# Receiver.net
KiCad netlist of a schematic drawn in Altium Designer
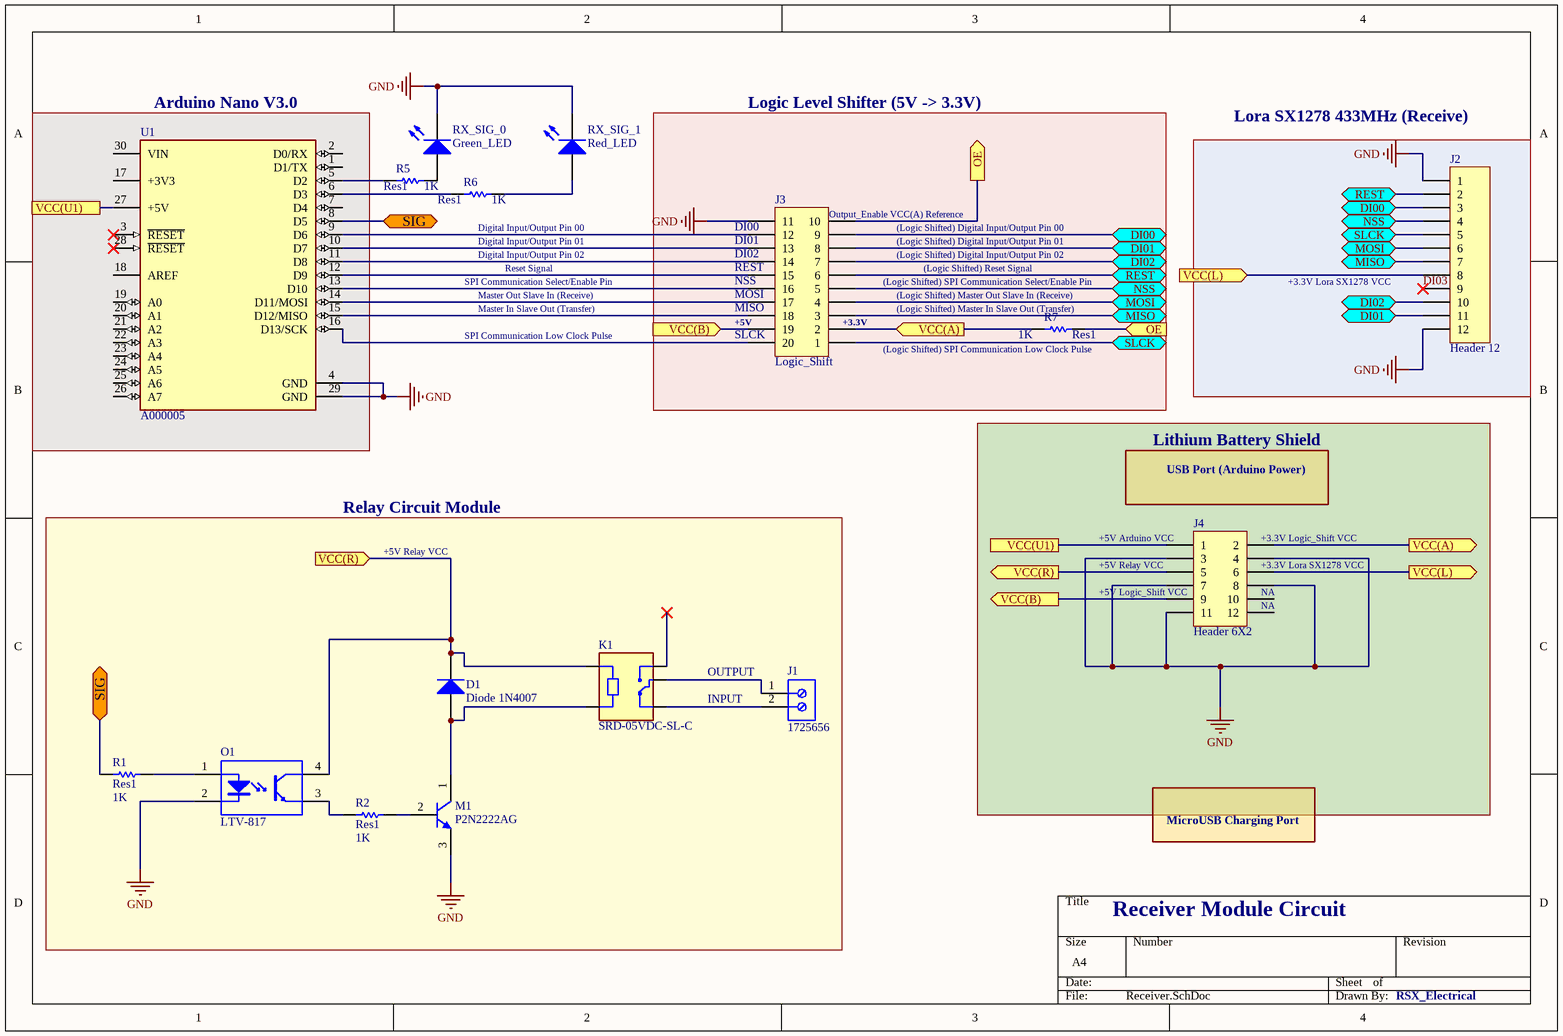
[diagram p0: Receiver.SchDoc]

(export (version "E")
  (design (tool "Eeschema 10.0.6"))
  (components
    (comp (ref "D1")
      (value "Diode 1N4007")
      (footprint "DO-41")
      (description "1 Amp General Purpose Rectifier")
      (fields (field (name "PUBLISHER") "Altium Limited"))
      (libsource (lib "Miscellaneous Devices") (part "Diode 1N4007"))
    )
    (comp (ref "J1")
      (value "1725656")
      (footprint "PHOE-1725656-2")
      (description "Male Header, Pitch 2.54 mm, 1 x 2 Position, Height 9 mm, Tail Length 3.5 mm")
      (fields (field (name "MANUFACTURER") "Phoenix Contact"))
      (libsource (lib "Altium Content Vault") (part "CN-1P-F-TB2"))
    )
    (comp (ref "J2")
      (value "Header 12")
      (footprint "LORA Sx1278")
      (description "Header, 12-Pin")
      (fields (field (name "PUBLISHER") "Altium Limited"))
      (libsource (lib "Miscellaneous Connectors") (part "Header 12"))
    )
    (comp (ref "J3")
      (value "Logic_Shift")
      (footprint "DIP2SSOP20")
      (description "Header, 10-Pin, Dual row")
      (fields (field (name "PUBLISHER") "Altium Limited"))
      (libsource (lib "Miscellaneous Connectors") (part "Header 10X2"))
    )
    (comp (ref "J4")
      (value "Header 6X2")
      (footprint "3.3V/5V Battery Shield")
      (description "Header, 6-Pin, Dual row")
      (fields (field (name "PUBLISHER") "Altium Limited"))
      (libsource (lib "Miscellaneous Connectors") (part "Header 6X2"))
    )
    (comp (ref "K1")
      (value "SRD-05VDC-SL-C")
      (footprint "RELAY_SRD-05VDC-SL-C")
      (fields (field (name "MF") "Songle Relay"))
      (libsource (lib "SRD-05VDC-SL-C") (part "SRD-05VDC-SL-C"))
    )
    (comp (ref "M1")
      (value "P2N2222AG")
      (footprint "ONSC-TO-92-3-29-11")
      (description "Amplifier Transistor, NPN Silicon, 3-Pin TO-92, Pb-Free, Bulk Box")
      (fields (field (name "MANUFACTURER") "On Semiconductor"))
      (libsource (lib "Altium Content Vault") (part "ONSC-NPN-C1B2E3-3"))
    )
    (comp (ref "O1")
      (value "LTV-817")
      (footprint "LTST-LTV-817-4")
      (fields (field (name "MANUFACTURER") "Lite-On"))
      (libsource (lib "Altium Content Vault") (part "OPTO-AKEC-4"))
    )
    (comp (ref "R1")
      (value "Res1")
      (footprint "AXIAL-0.3")
      (description "Resistor")
      (fields (field (name "ALTIUM_VALUE") "1K") (field (name "PUBLISHER") "Altium Limited"))
      (libsource (lib "Miscellaneous Devices") (part "Res1"))
    )
    (comp (ref "R2")
      (value "Res1")
      (footprint "AXIAL-0.3")
      (description "Resistor")
      (fields (field (name "ALTIUM_VALUE") "1K") (field (name "PUBLISHER") "Altium Limited"))
      (libsource (lib "Miscellaneous Devices") (part "Res1"))
    )
    (comp (ref "R5")
      (value "Res1")
      (footprint "AXIAL-0.3")
      (description "Resistor")
      (fields (field (name "ALTIUM_VALUE") "1K") (field (name "PUBLISHER") "Altium Limited"))
      (libsource (lib "Miscellaneous Devices") (part "Res1"))
    )
    (comp (ref "R6")
      (value "Res1")
      (footprint "AXIAL-0.3")
      (description "Resistor")
      (fields (field (name "ALTIUM_VALUE") "1K") (field (name "PUBLISHER") "Altium Limited"))
      (libsource (lib "Miscellaneous Devices") (part "Res1"))
    )
    (comp (ref "R7")
      (value "Res1")
      (footprint "AXIAL-0.3")
      (description "Resistor")
      (fields (field (name "ALTIUM_VALUE") "1K") (field (name "PUBLISHER") "Altium Limited"))
      (libsource (lib "Miscellaneous Devices") (part "Res1"))
    )
    (comp (ref "RX_SIG_0")
      (value "Green_LED")
      (footprint "LED-0")
      (description "Typical INFRARED GaAs LED")
      (fields (field (name "PUBLISHER") "Altium Limited"))
      (libsource (lib "Miscellaneous Devices") (part "LED0"))
    )
    (comp (ref "RX_SIG_1")
      (value "Red_LED")
      (footprint "LED-0")
      (description "Typical INFRARED GaAs LED")
      (fields (field (name "PUBLISHER") "Altium Limited"))
      (libsource (lib "Miscellaneous Devices") (part "LED0"))
    )
    (comp (ref "U1")
      (value "A000005")
      (footprint "FP-A000005-MFG")
      (description "ARDUINO NANO ATMEGA328 EVAL BRD")
      (libsource (lib "Altium Content Vault") (part "d190c066e99afd1c6882cf92e11b2cc"))
    )
  )
  (nets
    (net (code "1") (name "/DI00") (class "Default")
      (node (ref "J2") (pin "3") (pinfunction "3_3") (pintype "passive"))
      (node (ref "J3") (pin "9") (pinfunction "9_9") (pintype "passive"))
    )
    (net (code "2") (name "/DI01") (class "Default")
      (node (ref "J2") (pin "11") (pinfunction "11_11") (pintype "passive"))
      (node (ref "J3") (pin "8") (pinfunction "8_8") (pintype "passive"))
    )
    (net (code "3") (name "/DI02") (class "Default")
      (node (ref "J2") (pin "10") (pinfunction "10_10") (pintype "passive"))
      (node (ref "J3") (pin "7") (pinfunction "7_7") (pintype "passive"))
    )
    (net (code "4") (name "/DI03") (class "Default")
      (node (ref "J2") (pin "9") (pinfunction "9_9") (pintype "passive+no_connect"))
    )
    (net (code "5") (name "/MISO") (class "Default")
      (node (ref "J2") (pin "7") (pinfunction "7_7") (pintype "passive"))
      (node (ref "J3") (pin "3") (pinfunction "3_3") (pintype "passive"))
    )
    (net (code "6") (name "/MOSI") (class "Default")
      (node (ref "J2") (pin "6") (pinfunction "6_6") (pintype "passive"))
      (node (ref "J3") (pin "4") (pinfunction "4_4") (pintype "passive"))
    )
    (net (code "7") (name "/NSS") (class "Default")
      (node (ref "J2") (pin "4") (pinfunction "4_4") (pintype "passive"))
      (node (ref "J3") (pin "5") (pinfunction "5_5") (pintype "passive"))
    )
    (net (code "8") (name "/OE") (class "Default")
      (node (ref "J3") (pin "10") (pinfunction "10_10") (pintype "passive"))
      (node (ref "R7") (pin "1") (pinfunction "1_1") (pintype "passive"))
    )
    (net (code "9") (name "/REST") (class "Default")
      (node (ref "J2") (pin "2") (pinfunction "2_2") (pintype "passive"))
      (node (ref "J3") (pin "6") (pinfunction "6_6") (pintype "passive"))
    )
    (net (code "10") (name "/SIG") (class "Default")
      (node (ref "R1") (pin "2") (pinfunction "2_2") (pintype "passive"))
      (node (ref "U1") (pin "8") (pinfunction "D5_8") (pintype "bidirectional"))
    )
    (net (code "11") (name "/SLCK") (class "Default")
      (node (ref "J2") (pin "5") (pinfunction "5_5") (pintype "passive"))
      (node (ref "J3") (pin "1") (pinfunction "1_1") (pintype "passive"))
    )
    (net (code "12") (name "/VCC(A)") (class "Default")
      (node (ref "J3") (pin "2") (pinfunction "2_2") (pintype "passive"))
      (node (ref "J4") (pin "2") (pinfunction "2_2") (pintype "passive"))
      (node (ref "R7") (pin "2") (pinfunction "2_2") (pintype "passive"))
    )
    (net (code "13") (name "/VCC(B)") (class "Default")
      (node (ref "J3") (pin "19") (pinfunction "19_19") (pintype "passive"))
      (node (ref "J4") (pin "9") (pinfunction "9_9") (pintype "passive"))
    )
    (net (code "14") (name "/VCC(L)") (class "Default")
      (node (ref "J2") (pin "8") (pinfunction "8_8") (pintype "passive"))
      (node (ref "J4") (pin "6") (pinfunction "6_6") (pintype "passive"))
    )
    (net (code "15") (name "/VCC(R)") (class "Default")
      (node (ref "D1") (pin "2") (pinfunction "K_2") (pintype "passive"))
      (node (ref "J4") (pin "5") (pinfunction "5_5") (pintype "passive"))
      (node (ref "K1") (pin "A1") (pinfunction "A1_A1") (pintype "passive"))
      (node (ref "O1") (pin "4") (pinfunction "COLLECTOR_4") (pintype "passive"))
    )
    (net (code "16") (name "/VCC(U1)") (class "Default")
      (node (ref "J4") (pin "1") (pinfunction "1_1") (pintype "passive"))
      (node (ref "U1") (pin "27") (pinfunction "+5V_27") (pintype "power_in"))
    )
    (net (code "17") (name "GND") (class "Default")
      (node (ref "J2") (pin "1") (pinfunction "1_1") (pintype "passive"))
      (node (ref "J2") (pin "12") (pinfunction "12_12") (pintype "passive"))
      (node (ref "J3") (pin "11") (pinfunction "11_11") (pintype "passive"))
      (node (ref "J4") (pin "11") (pinfunction "11_11") (pintype "passive"))
      (node (ref "J4") (pin "3") (pinfunction "3_3") (pintype "passive"))
      (node (ref "J4") (pin "4") (pinfunction "4_4") (pintype "passive"))
      (node (ref "J4") (pin "7") (pinfunction "7_7") (pintype "passive"))
      (node (ref "J4") (pin "8") (pinfunction "8_8") (pintype "passive"))
      (node (ref "M1") (pin "3") (pinfunction "E_3") (pintype "passive"))
      (node (ref "O1") (pin "2") (pinfunction "CATHODE_2") (pintype "passive"))
      (node (ref "RX_SIG_0") (pin "2") (pinfunction "K_2") (pintype "passive"))
      (node (ref "RX_SIG_1") (pin "2") (pinfunction "K_2") (pintype "passive"))
      (node (ref "U1") (pin "29") (pinfunction "GND_29") (pintype "power_in"))
      (node (ref "U1") (pin "4") (pinfunction "GND_4") (pintype "power_in"))
    )
    (net (code "18") (name "Net-(D1-A)") (class "Default")
      (node (ref "D1") (pin "1") (pinfunction "A_1") (pintype "passive"))
      (node (ref "K1") (pin "A2") (pinfunction "A2_A2") (pintype "passive"))
      (node (ref "M1") (pin "1") (pinfunction "C_1") (pintype "passive"))
    )
    (net (code "19") (name "Net-(J1-Pad1)") (class "Default")
      (node (ref "J1") (pin "1") (pinfunction "1_1") (pintype "passive"))
      (node (ref "K1") (pin "COM") (pinfunction "COM_COM") (pintype "passive"))
    )
    (net (code "20") (name "Net-(J1-Pad2)") (class "Default")
      (node (ref "J1") (pin "2") (pinfunction "2_2") (pintype "passive"))
      (node (ref "K1") (pin "NC") (pinfunction "NC_NC") (pintype "passive"))
    )
    (net (code "21") (name "Net-(M1-B)") (class "Default")
      (node (ref "M1") (pin "2") (pinfunction "B_2") (pintype "passive"))
      (node (ref "R2") (pin "2") (pinfunction "2_2") (pintype "passive"))
    )
    (net (code "22") (name "Net-(O1-ANODE)") (class "Default")
      (node (ref "O1") (pin "1") (pinfunction "ANODE_1") (pintype "passive"))
      (node (ref "R1") (pin "1") (pinfunction "1_1") (pintype "passive"))
    )
    (net (code "23") (name "Net-(O1-EMITTER)") (class "Default")
      (node (ref "O1") (pin "3") (pinfunction "EMITTER_3") (pintype "passive"))
      (node (ref "R2") (pin "1") (pinfunction "1_1") (pintype "passive"))
    )
    (net (code "24") (name "Net-(RX_SIG_0-A)") (class "Default")
      (node (ref "R5") (pin "1") (pinfunction "1_1") (pintype "passive"))
      (node (ref "RX_SIG_0") (pin "1") (pinfunction "A_1") (pintype "passive"))
    )
    (net (code "25") (name "Net-(RX_SIG_1-A)") (class "Default")
      (node (ref "R6") (pin "1") (pinfunction "1_1") (pintype "passive"))
      (node (ref "RX_SIG_1") (pin "1") (pinfunction "A_1") (pintype "passive"))
    )
    (net (code "26") (name "Net-(U1-D2)") (class "Default")
      (node (ref "R5") (pin "2") (pinfunction "2_2") (pintype "passive"))
      (node (ref "U1") (pin "5") (pinfunction "D2_5") (pintype "bidirectional"))
    )
    (net (code "27") (name "Net-(U1-D3)") (class "Default")
      (node (ref "R6") (pin "2") (pinfunction "2_2") (pintype "passive"))
      (node (ref "U1") (pin "6") (pinfunction "D3_6") (pintype "bidirectional"))
    )
    (net (code "28") (name "Net-(U1-D6)") (class "Default")
      (node (ref "J3") (pin "12") (pinfunction "12_12") (pintype "passive"))
      (node (ref "U1") (pin "9") (pinfunction "D6_9") (pintype "bidirectional"))
    )
    (net (code "29") (name "Net-(U1-D7)") (class "Default")
      (node (ref "J3") (pin "13") (pinfunction "13_13") (pintype "passive"))
      (node (ref "U1") (pin "10") (pinfunction "D7_10") (pintype "bidirectional"))
    )
    (net (code "30") (name "Net-(U1-D8)") (class "Default")
      (node (ref "J3") (pin "14") (pinfunction "14_14") (pintype "passive"))
      (node (ref "U1") (pin "11") (pinfunction "D8_11") (pintype "bidirectional"))
    )
    (net (code "31") (name "Net-(U1-D9)") (class "Default")
      (node (ref "J3") (pin "15") (pinfunction "15_15") (pintype "passive"))
      (node (ref "U1") (pin "12") (pinfunction "D9_12") (pintype "bidirectional"))
    )
    (net (code "32") (name "Net-(U1-D10)") (class "Default")
      (node (ref "J3") (pin "16") (pinfunction "16_16") (pintype "passive"))
      (node (ref "U1") (pin "13") (pinfunction "D10_13") (pintype "bidirectional"))
    )
    (net (code "33") (name "Net-(U1-D11{slash}MOSI)") (class "Default")
      (node (ref "J3") (pin "17") (pinfunction "17_17") (pintype "passive"))
      (node (ref "U1") (pin "14") (pinfunction "D11/MOSI_14") (pintype "bidirectional"))
    )
    (net (code "34") (name "Net-(U1-D12{slash}MISO)") (class "Default")
      (node (ref "J3") (pin "18") (pinfunction "18_18") (pintype "passive"))
      (node (ref "U1") (pin "15") (pinfunction "D12/MISO_15") (pintype "bidirectional"))
    )
    (net (code "35") (name "Net-(U1-D13{slash}SCK)") (class "Default")
      (node (ref "J3") (pin "20") (pinfunction "20_20") (pintype "passive"))
      (node (ref "U1") (pin "16") (pinfunction "D13/SCK_16") (pintype "bidirectional"))
    )
    (net (code "36") (name "unconnected-(J4-Pad10)") (class "Default")
      (node (ref "J4") (pin "10") (pinfunction "10_10") (pintype "passive"))
    )
    (net (code "37") (name "unconnected-(J4-Pad12)") (class "Default")
      (node (ref "J4") (pin "12") (pinfunction "12_12") (pintype "passive"))
    )
    (net (code "38") (name "unconnected-(K1-PadNO)") (class "Default")
      (node (ref "K1") (pin "NO") (pinfunction "NO_NO") (pintype "passive+no_connect"))
    )
    (net (code "39") (name "unconnected-(U1-+3V3-Pad17)") (class "Default")
      (node (ref "U1") (pin "17") (pinfunction "+3V3_17") (pintype "power_in"))
    )
    (net (code "40") (name "unconnected-(U1-A0-Pad19)") (class "Default")
      (node (ref "U1") (pin "19") (pinfunction "A0_19") (pintype "bidirectional"))
    )
    (net (code "41") (name "unconnected-(U1-A1-Pad20)") (class "Default")
      (node (ref "U1") (pin "20") (pinfunction "A1_20") (pintype "bidirectional"))
    )
    (net (code "42") (name "unconnected-(U1-A2-Pad21)") (class "Default")
      (node (ref "U1") (pin "21") (pinfunction "A2_21") (pintype "bidirectional"))
    )
    (net (code "43") (name "unconnected-(U1-A3-Pad22)") (class "Default")
      (node (ref "U1") (pin "22") (pinfunction "A3_22") (pintype "bidirectional"))
    )
    (net (code "44") (name "unconnected-(U1-A4-Pad23)") (class "Default")
      (node (ref "U1") (pin "23") (pinfunction "A4_23") (pintype "bidirectional"))
    )
    (net (code "45") (name "unconnected-(U1-A5-Pad24)") (class "Default")
      (node (ref "U1") (pin "24") (pinfunction "A5_24") (pintype "bidirectional"))
    )
    (net (code "46") (name "unconnected-(U1-A6-Pad25)") (class "Default")
      (node (ref "U1") (pin "25") (pinfunction "A6_25") (pintype "bidirectional"))
    )
    (net (code "47") (name "unconnected-(U1-A7-Pad26)") (class "Default")
      (node (ref "U1") (pin "26") (pinfunction "A7_26") (pintype "bidirectional"))
    )
    (net (code "48") (name "unconnected-(U1-AREF-Pad18)") (class "Default")
      (node (ref "U1") (pin "18") (pinfunction "AREF_18") (pintype "passive"))
    )
    (net (code "49") (name "unconnected-(U1-D0{slash}RX-Pad2)") (class "Default")
      (node (ref "U1") (pin "2") (pinfunction "D0/RX_2") (pintype "bidirectional"))
    )
    (net (code "50") (name "unconnected-(U1-D1{slash}TX-Pad1)") (class "Default")
      (node (ref "U1") (pin "1") (pinfunction "D1/TX_1") (pintype "bidirectional"))
    )
    (net (code "51") (name "unconnected-(U1-D4-Pad7)") (class "Default")
      (node (ref "U1") (pin "7") (pinfunction "D4_7") (pintype "bidirectional"))
    )
    (net (code "52") (name "unconnected-(U1-VIN-Pad30)") (class "Default")
      (node (ref "U1") (pin "30") (pinfunction "VIN_30") (pintype "power_in"))
    )
    (net (code "53") (name "unconnected-(U1-~{RESET}-Pad3)") (class "Default")
      (node (ref "U1") (pin "3") (pinfunction "~{RESET}_3") (pintype "input+no_connect"))
    )
    (net (code "54") (name "unconnected-(U1-~{RESET}-Pad28)") (class "Default")
      (node (ref "U1") (pin "28") (pinfunction "~{RESET}_28") (pintype "input+no_connect"))
    )
  )
)
